# Sheet1.net
KiCad netlist of a schematic drawn in Altium Designer
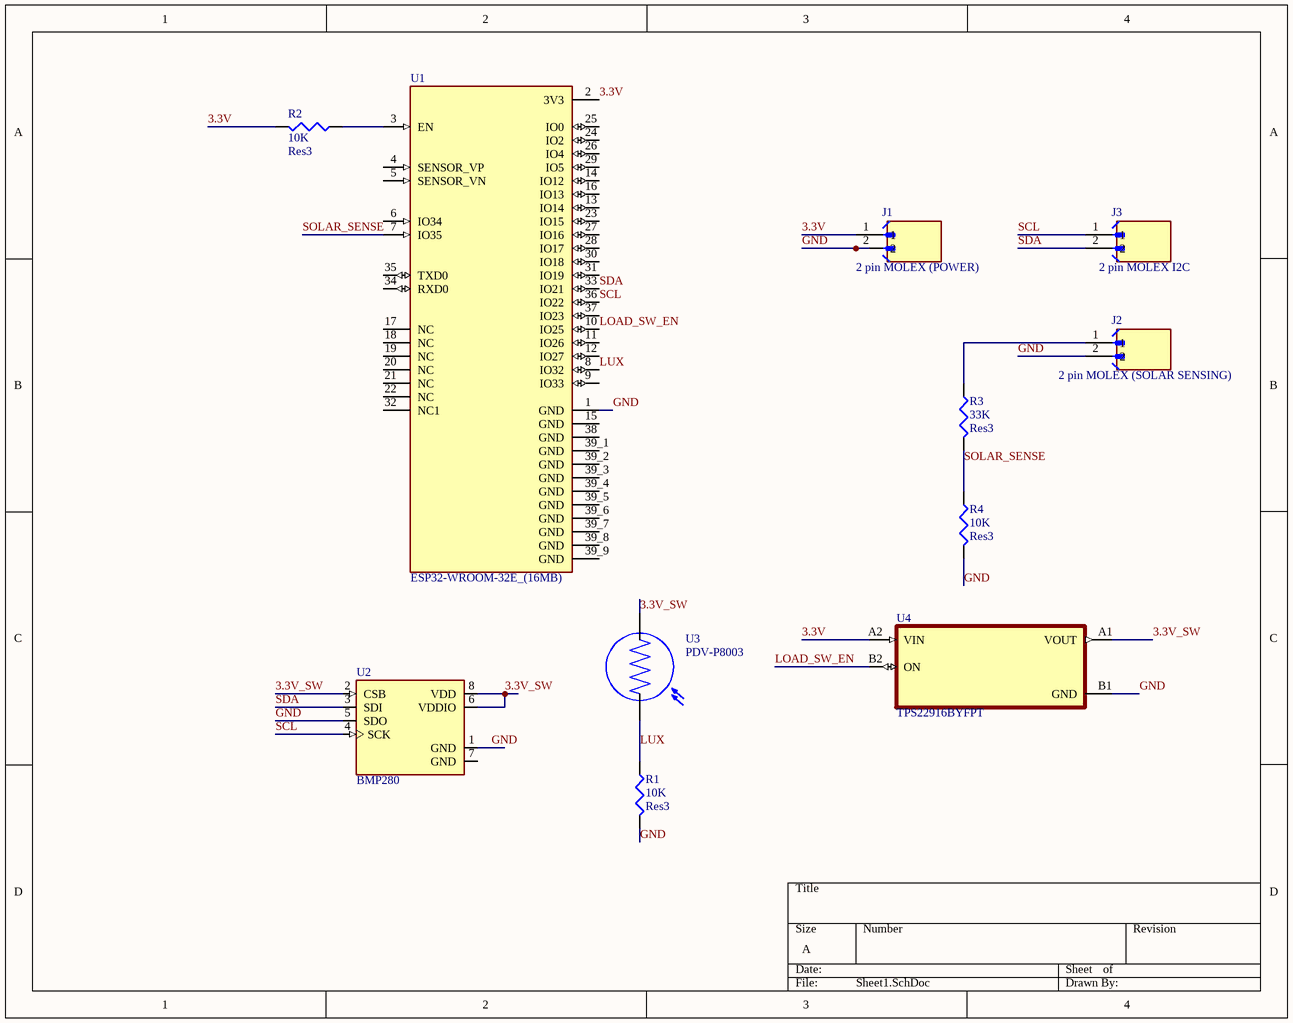
[diagram p0: Sheet1.SchDoc]

(export (version "E")
  (design (tool "Eeschema 10.0.6"))
  (components
    (comp (ref "J1")
      (value "2 pin MOLEX (POWER)")
      (footprint "TE_5-1775443-2")
      (description "Conn High Performance Interconnect HDR 2 POS 1.5mm Solder ST SMD T/R")
      (fields (field (name "MF") "TE Connectivity") (field (name "MP") "5-1775443-2"))
      (libsource (lib "5-1775443-2") (part "5-1775443-2"))
    )
    (comp (ref "J2")
      (value "2 pin MOLEX (SOLAR SENSING)")
      (footprint "TE_5-1775443-2")
      (description "Conn High Performance Interconnect HDR 2 POS 1.5mm Solder ST SMD T/R")
      (fields (field (name "MF") "TE Connectivity") (field (name "MP") "5-1775443-2"))
      (libsource (lib "5-1775443-2") (part "5-1775443-2"))
    )
    (comp (ref "J3")
      (value "2 pin MOLEX I2C")
      (footprint "TE_5-1775443-2")
      (description "Conn High Performance Interconnect HDR 2 POS 1.5mm Solder ST SMD T/R")
      (fields (field (name "MF") "TE Connectivity") (field (name "MP") "5-1775443-2"))
      (libsource (lib "5-1775443-2") (part "5-1775443-2"))
    )
    (comp (ref "R1")
      (value "Res3")
      (footprint "J1-0603")
      (description "Resistor")
      (fields (field (name "ALTIUM_VALUE") "10K") (field (name "PUBLISHER") "Altium Limited"))
      (libsource (lib "Miscellaneous Devices") (part "Res3"))
    )
    (comp (ref "R2")
      (value "Res3")
      (footprint "J1-0603")
      (description "Resistor")
      (fields (field (name "ALTIUM_VALUE") "10K") (field (name "PUBLISHER") "Altium Limited"))
      (libsource (lib "Miscellaneous Devices") (part "Res3"))
    )
    (comp (ref "R3")
      (value "Res3")
      (footprint "J1-0603")
      (description "Resistor")
      (fields (field (name "ALTIUM_VALUE") "33K") (field (name "PUBLISHER") "Altium Limited"))
      (libsource (lib "Miscellaneous Devices") (part "Res3"))
    )
    (comp (ref "R4")
      (value "Res3")
      (footprint "J1-0603")
      (description "Resistor")
      (fields (field (name "ALTIUM_VALUE") "10K") (field (name "PUBLISHER") "Altium Limited"))
      (libsource (lib "Miscellaneous Devices") (part "Res3"))
    )
    (comp (ref "U1")
      (value "ESP32-WROOM-32E_(16MB)")
      (footprint "XCVR_ESP32-WROOM-32E_(16MB)")
      (fields (field (name "MP") "ESP32-WROOM-32E (16MB)") (field (name "MF") "Espressif Systems"))
      (libsource (lib "ESP32-WROOM-32E__16MB_") (part "ESP32-WROOM-32E_(16MB)"))
    )
    (comp (ref "U2")
      (value "BMP280")
      (footprint "XDCR_BMP280")
      (description "BMP280 Absolute Barometric Pressure Sensor for Battery Powered Devices 2 x 2.5mm")
      (libsource (lib "BMP280") (part "BMP280"))
    )
    (comp (ref "U3")
      (value "PDV-P8003")
      (footprint "XDCR_PDV-P8003")
      (description "CdS Cells 520nm 16 ~ 33kOhms @ 10 lux")
      (fields (field (name "MF") "Advanced Photonix"))
      (libsource (lib "PDV-P8003") (part "PDV-P8003"))
    )
    (comp (ref "U4")
      (value "TPS22916BYFPT")
      (footprint "BGA4C40P2X2_77X77X50")
      (description "5.5-V, 2-A, 60-mÎ©, 10-nA leakage load switch with output discharge")
      (fields (field (name "MF") "Texas Instruments"))
      (libsource (lib "TPS22916BYFPT") (part "TPS22916BYFPT"))
    )
  )
  (nets
    (net (code "1") (name "/3.3V") (class "Default")
      (node (ref "J1") (pin "1") (pinfunction "1_1") (pintype "passive"))
      (node (ref "R2") (pin "2") (pinfunction "2_2") (pintype "passive"))
      (node (ref "U1") (pin "2") (pinfunction "3V3_2") (pintype "power_in"))
      (node (ref "U4") (pin "A2") (pinfunction "VIN_A2") (pintype "input"))
    )
    (net (code "2") (name "/3.3V_SW") (class "Default")
      (node (ref "U2") (pin "2") (pinfunction "CSB_2") (pintype "input"))
      (node (ref "U2") (pin "6") (pinfunction "VDDIO_6") (pintype "power_in"))
      (node (ref "U2") (pin "8") (pinfunction "VDD_8") (pintype "power_in"))
      (node (ref "U3") (pin "1") (pinfunction "1_1") (pintype "passive"))
      (node (ref "U4") (pin "A1") (pinfunction "VOUT_A1") (pintype "output"))
    )
    (net (code "3") (name "/GND") (class "Default")
      (node (ref "J1") (pin "2") (pinfunction "2_2") (pintype "passive"))
      (node (ref "J2") (pin "2") (pinfunction "2_2") (pintype "passive"))
      (node (ref "R1") (pin "2") (pinfunction "2_2") (pintype "passive"))
      (node (ref "R4") (pin "2") (pinfunction "2_2") (pintype "passive"))
      (node (ref "U1") (pin "1") (pinfunction "GND_1") (pintype "power_in"))
      (node (ref "U2") (pin "1") (pinfunction "GND_1") (pintype "power_in"))
      (node (ref "U2") (pin "5") (pinfunction "SDO_5") (pintype "bidirectional"))
      (node (ref "U4") (pin "B1") (pinfunction "GND_B1") (pintype "power_in"))
    )
    (net (code "4") (name "/LOAD_SW_EN") (class "Default")
      (node (ref "U1") (pin "10") (pinfunction "IO25_10") (pintype "bidirectional"))
      (node (ref "U4") (pin "B2") (pinfunction "ON_B2") (pintype "bidirectional"))
    )
    (net (code "5") (name "/LUX") (class "Default")
      (node (ref "R1") (pin "1") (pinfunction "1_1") (pintype "passive"))
      (node (ref "U1") (pin "8") (pinfunction "IO32_8") (pintype "bidirectional"))
      (node (ref "U3") (pin "2") (pinfunction "2_2") (pintype "passive"))
    )
    (net (code "6") (name "/SCL") (class "Default")
      (node (ref "J3") (pin "1") (pinfunction "1_1") (pintype "passive"))
      (node (ref "U1") (pin "36") (pinfunction "IO22_36") (pintype "bidirectional"))
      (node (ref "U2") (pin "4") (pinfunction "SCK_4") (pintype "input"))
    )
    (net (code "7") (name "/SDA") (class "Default")
      (node (ref "J3") (pin "2") (pinfunction "2_2") (pintype "passive"))
      (node (ref "U1") (pin "33") (pinfunction "IO21_33") (pintype "bidirectional"))
      (node (ref "U2") (pin "3") (pinfunction "SDI_3") (pintype "bidirectional"))
    )
    (net (code "8") (name "/SOLAR_SENSE") (class "Default")
      (node (ref "R3") (pin "2") (pinfunction "2_2") (pintype "passive"))
      (node (ref "R4") (pin "1") (pinfunction "1_1") (pintype "passive"))
      (node (ref "U1") (pin "7") (pinfunction "IO35_7") (pintype "input"))
    )
    (net (code "9") (name "Net-(J2-Pad1)") (class "Default")
      (node (ref "J2") (pin "1") (pinfunction "1_1") (pintype "passive"))
      (node (ref "R3") (pin "1") (pinfunction "1_1") (pintype "passive"))
    )
    (net (code "10") (name "Net-(U1-EN)") (class "Default")
      (node (ref "R2") (pin "1") (pinfunction "1_1") (pintype "passive"))
      (node (ref "U1") (pin "3") (pinfunction "EN_3") (pintype "input"))
    )
    (net (code "11") (name "unconnected-(U1-GND-Pad15)") (class "Default")
      (node (ref "U1") (pin "15") (pinfunction "GND_15") (pintype "power_in"))
    )
    (net (code "12") (name "unconnected-(U1-GND-Pad38)") (class "Default")
      (node (ref "U1") (pin "38") (pinfunction "GND_38") (pintype "power_in"))
    )
    (net (code "13") (name "unconnected-(U1-GND-Pad39_1)") (class "Default")
      (node (ref "U1") (pin "39_1") (pinfunction "GND_39_1") (pintype "power_in"))
    )
    (net (code "14") (name "unconnected-(U1-GND-Pad39_2)") (class "Default")
      (node (ref "U1") (pin "39_2") (pinfunction "GND_39_2") (pintype "power_in"))
    )
    (net (code "15") (name "unconnected-(U1-GND-Pad39_3)") (class "Default")
      (node (ref "U1") (pin "39_3") (pinfunction "GND_39_3") (pintype "power_in"))
    )
    (net (code "16") (name "unconnected-(U1-GND-Pad39_4)") (class "Default")
      (node (ref "U1") (pin "39_4") (pinfunction "GND_39_4") (pintype "power_in"))
    )
    (net (code "17") (name "unconnected-(U1-GND-Pad39_5)") (class "Default")
      (node (ref "U1") (pin "39_5") (pinfunction "GND_39_5") (pintype "power_in"))
    )
    (net (code "18") (name "unconnected-(U1-GND-Pad39_6)") (class "Default")
      (node (ref "U1") (pin "39_6") (pinfunction "GND_39_6") (pintype "power_in"))
    )
    (net (code "19") (name "unconnected-(U1-GND-Pad39_7)") (class "Default")
      (node (ref "U1") (pin "39_7") (pinfunction "GND_39_7") (pintype "power_in"))
    )
    (net (code "20") (name "unconnected-(U1-GND-Pad39_8)") (class "Default")
      (node (ref "U1") (pin "39_8") (pinfunction "GND_39_8") (pintype "power_in"))
    )
    (net (code "21") (name "unconnected-(U1-GND-Pad39_9)") (class "Default")
      (node (ref "U1") (pin "39_9") (pinfunction "GND_39_9") (pintype "power_in"))
    )
    (net (code "22") (name "unconnected-(U1-IO0-Pad25)") (class "Default")
      (node (ref "U1") (pin "25") (pinfunction "IO0_25") (pintype "bidirectional"))
    )
    (net (code "23") (name "unconnected-(U1-IO2-Pad24)") (class "Default")
      (node (ref "U1") (pin "24") (pinfunction "IO2_24") (pintype "bidirectional"))
    )
    (net (code "24") (name "unconnected-(U1-IO4-Pad26)") (class "Default")
      (node (ref "U1") (pin "26") (pinfunction "IO4_26") (pintype "bidirectional"))
    )
    (net (code "25") (name "unconnected-(U1-IO5-Pad29)") (class "Default")
      (node (ref "U1") (pin "29") (pinfunction "IO5_29") (pintype "bidirectional"))
    )
    (net (code "26") (name "unconnected-(U1-IO12-Pad14)") (class "Default")
      (node (ref "U1") (pin "14") (pinfunction "IO12_14") (pintype "bidirectional"))
    )
    (net (code "27") (name "unconnected-(U1-IO13-Pad16)") (class "Default")
      (node (ref "U1") (pin "16") (pinfunction "IO13_16") (pintype "bidirectional"))
    )
    (net (code "28") (name "unconnected-(U1-IO14-Pad13)") (class "Default")
      (node (ref "U1") (pin "13") (pinfunction "IO14_13") (pintype "bidirectional"))
    )
    (net (code "29") (name "unconnected-(U1-IO15-Pad23)") (class "Default")
      (node (ref "U1") (pin "23") (pinfunction "IO15_23") (pintype "bidirectional"))
    )
    (net (code "30") (name "unconnected-(U1-IO16-Pad27)") (class "Default")
      (node (ref "U1") (pin "27") (pinfunction "IO16_27") (pintype "bidirectional"))
    )
    (net (code "31") (name "unconnected-(U1-IO17-Pad28)") (class "Default")
      (node (ref "U1") (pin "28") (pinfunction "IO17_28") (pintype "bidirectional"))
    )
    (net (code "32") (name "unconnected-(U1-IO18-Pad30)") (class "Default")
      (node (ref "U1") (pin "30") (pinfunction "IO18_30") (pintype "bidirectional"))
    )
    (net (code "33") (name "unconnected-(U1-IO19-Pad31)") (class "Default")
      (node (ref "U1") (pin "31") (pinfunction "IO19_31") (pintype "bidirectional"))
    )
    (net (code "34") (name "unconnected-(U1-IO23-Pad37)") (class "Default")
      (node (ref "U1") (pin "37") (pinfunction "IO23_37") (pintype "bidirectional"))
    )
    (net (code "35") (name "unconnected-(U1-IO26-Pad11)") (class "Default")
      (node (ref "U1") (pin "11") (pinfunction "IO26_11") (pintype "bidirectional"))
    )
    (net (code "36") (name "unconnected-(U1-IO27-Pad12)") (class "Default")
      (node (ref "U1") (pin "12") (pinfunction "IO27_12") (pintype "bidirectional"))
    )
    (net (code "37") (name "unconnected-(U1-IO33-Pad9)") (class "Default")
      (node (ref "U1") (pin "9") (pinfunction "IO33_9") (pintype "bidirectional"))
    )
    (net (code "38") (name "unconnected-(U1-IO34-Pad6)") (class "Default")
      (node (ref "U1") (pin "6") (pinfunction "IO34_6") (pintype "input"))
    )
    (net (code "39") (name "unconnected-(U1-NC-Pad17)") (class "Default")
      (node (ref "U1") (pin "17") (pinfunction "NC_17") (pintype "passive"))
    )
    (net (code "40") (name "unconnected-(U1-NC-Pad18)") (class "Default")
      (node (ref "U1") (pin "18") (pinfunction "NC_18") (pintype "passive"))
    )
    (net (code "41") (name "unconnected-(U1-NC-Pad19)") (class "Default")
      (node (ref "U1") (pin "19") (pinfunction "NC_19") (pintype "passive"))
    )
    (net (code "42") (name "unconnected-(U1-NC-Pad20)") (class "Default")
      (node (ref "U1") (pin "20") (pinfunction "NC_20") (pintype "passive"))
    )
    (net (code "43") (name "unconnected-(U1-NC-Pad21)") (class "Default")
      (node (ref "U1") (pin "21") (pinfunction "NC_21") (pintype "passive"))
    )
    (net (code "44") (name "unconnected-(U1-NC-Pad22)") (class "Default")
      (node (ref "U1") (pin "22") (pinfunction "NC_22") (pintype "passive"))
    )
    (net (code "45") (name "unconnected-(U1-NC1-Pad32)") (class "Default")
      (node (ref "U1") (pin "32") (pinfunction "NC1_32") (pintype "passive"))
    )
    (net (code "46") (name "unconnected-(U1-RXD0-Pad34)") (class "Default")
      (node (ref "U1") (pin "34") (pinfunction "RXD0_34") (pintype "bidirectional"))
    )
    (net (code "47") (name "unconnected-(U1-SENSOR_VN-Pad5)") (class "Default")
      (node (ref "U1") (pin "5") (pinfunction "SENSOR_VN_5") (pintype "input"))
    )
    (net (code "48") (name "unconnected-(U1-SENSOR_VP-Pad4)") (class "Default")
      (node (ref "U1") (pin "4") (pinfunction "SENSOR_VP_4") (pintype "input"))
    )
    (net (code "49") (name "unconnected-(U1-TXD0-Pad35)") (class "Default")
      (node (ref "U1") (pin "35") (pinfunction "TXD0_35") (pintype "bidirectional"))
    )
    (net (code "50") (name "unconnected-(U2-GND-Pad7)") (class "Default")
      (node (ref "U2") (pin "7") (pinfunction "GND_7") (pintype "power_in"))
    )
  )
)
